# 2_DRAM.net
KiCad netlist of a schematic drawn in Altium Designer
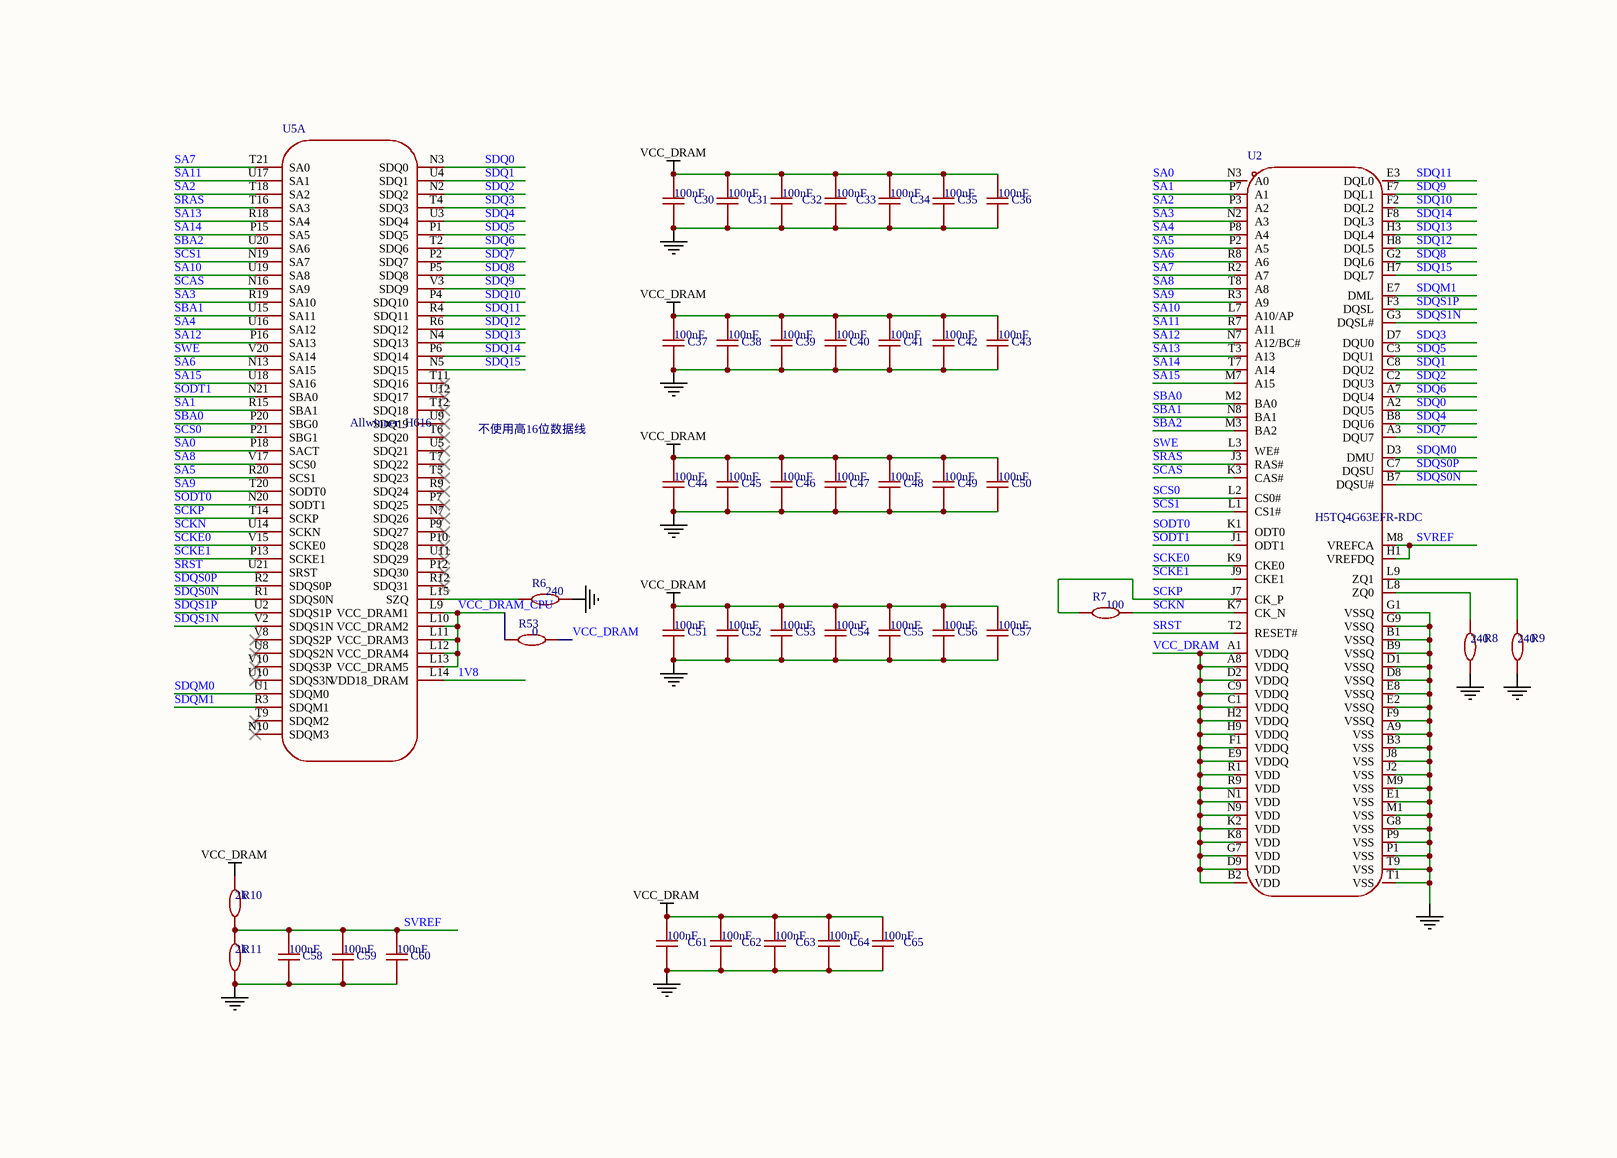
[diagram p0: 2_DRAM.schdoc]

(export (version "E")
  (design (tool "Eeschema 10.0.6"))
  (components
    (comp (ref "C30")
      (value "100nF")
      (footprint "PCB:C0402-NSK")
      (libsource (lib "PCB_Project") (part "CAP_0402"))
    )
    (comp (ref "C31")
      (value "100nF")
      (footprint "PCB:C0402-NSK")
      (libsource (lib "PCB_Project") (part "CAP_0402"))
    )
    (comp (ref "C32")
      (value "100nF")
      (footprint "PCB:C0402-NSK")
      (libsource (lib "PCB_Project") (part "CAP_0402"))
    )
    (comp (ref "C33")
      (value "100nF")
      (footprint "PCB:C0402-NSK")
      (libsource (lib "PCB_Project") (part "CAP_0402"))
    )
    (comp (ref "C34")
      (value "100nF")
      (footprint "PCB:C0402-NSK")
      (libsource (lib "PCB_Project") (part "CAP_0402"))
    )
    (comp (ref "C35")
      (value "100nF")
      (footprint "PCB:C0402-NSK")
      (libsource (lib "PCB_Project") (part "CAP_0402"))
    )
    (comp (ref "C36")
      (value "100nF")
      (footprint "PCB:C0402-NSK")
      (libsource (lib "PCB_Project") (part "CAP_0402"))
    )
    (comp (ref "C37")
      (value "100nF")
      (footprint "PCB:C0402-NSK")
      (libsource (lib "PCB_Project") (part "CAP_0402"))
    )
    (comp (ref "C38")
      (value "100nF")
      (footprint "PCB:C0402-NSK")
      (libsource (lib "PCB_Project") (part "CAP_0402"))
    )
    (comp (ref "C39")
      (value "100nF")
      (footprint "PCB:C0402-NSK")
      (libsource (lib "PCB_Project") (part "CAP_0402"))
    )
    (comp (ref "C40")
      (value "100nF")
      (footprint "PCB:C0402-NSK")
      (libsource (lib "PCB_Project") (part "CAP_0402"))
    )
    (comp (ref "C41")
      (value "100nF")
      (footprint "PCB:C0402-NSK")
      (libsource (lib "PCB_Project") (part "CAP_0402"))
    )
    (comp (ref "C42")
      (value "100nF")
      (footprint "PCB:C0402-NSK")
      (libsource (lib "PCB_Project") (part "CAP_0402"))
    )
    (comp (ref "C43")
      (value "100nF")
      (footprint "PCB:C0402-NSK")
      (libsource (lib "PCB_Project") (part "CAP_0402"))
    )
    (comp (ref "C44")
      (value "100nF")
      (footprint "PCB:C0402-NSK")
      (libsource (lib "PCB_Project") (part "CAP_0402"))
    )
    (comp (ref "C45")
      (value "100nF")
      (footprint "PCB:C0402-NSK")
      (libsource (lib "PCB_Project") (part "CAP_0402"))
    )
    (comp (ref "C46")
      (value "100nF")
      (footprint "PCB:C0402-NSK")
      (libsource (lib "PCB_Project") (part "CAP_0402"))
    )
    (comp (ref "C47")
      (value "100nF")
      (footprint "PCB:C0402-NSK")
      (libsource (lib "PCB_Project") (part "CAP_0402"))
    )
    (comp (ref "C48")
      (value "100nF")
      (footprint "PCB:C0402-NSK")
      (libsource (lib "PCB_Project") (part "CAP_0402"))
    )
    (comp (ref "C49")
      (value "100nF")
      (footprint "PCB:C0402-NSK")
      (libsource (lib "PCB_Project") (part "CAP_0402"))
    )
    (comp (ref "C50")
      (value "100nF")
      (footprint "PCB:C0402-NSK")
      (libsource (lib "PCB_Project") (part "CAP_0402"))
    )
    (comp (ref "C51")
      (value "100nF")
      (footprint "PCB:C0402-NSK")
      (libsource (lib "PCB_Project") (part "CAP_0402"))
    )
    (comp (ref "C52")
      (value "100nF")
      (footprint "PCB:C0402-NSK")
      (libsource (lib "PCB_Project") (part "CAP_0402"))
    )
    (comp (ref "C53")
      (value "100nF")
      (footprint "PCB:C0402-NSK")
      (libsource (lib "PCB_Project") (part "CAP_0402"))
    )
    (comp (ref "C54")
      (value "100nF")
      (footprint "PCB:C0402-NSK")
      (libsource (lib "PCB_Project") (part "CAP_0402"))
    )
    (comp (ref "C55")
      (value "100nF")
      (footprint "PCB:C0402-NSK")
      (libsource (lib "PCB_Project") (part "CAP_0402"))
    )
    (comp (ref "C56")
      (value "100nF")
      (footprint "PCB:C0402-NSK")
      (libsource (lib "PCB_Project") (part "CAP_0402"))
    )
    (comp (ref "C57")
      (value "100nF")
      (footprint "PCB:C0402-NSK")
      (libsource (lib "PCB_Project") (part "CAP_0402"))
    )
    (comp (ref "C58")
      (value "100nF")
      (footprint "PCB:C0402-NSK")
      (libsource (lib "PCB_Project") (part "CAP_0402"))
    )
    (comp (ref "C59")
      (value "100nF")
      (footprint "PCB:C0402-NSK")
      (libsource (lib "PCB_Project") (part "CAP_0402"))
    )
    (comp (ref "C60")
      (value "100nF")
      (footprint "PCB:C0402-NSK")
      (libsource (lib "PCB_Project") (part "CAP_0402"))
    )
    (comp (ref "C61")
      (value "100nF")
      (footprint "PCB:C0402-NSK")
      (libsource (lib "PCB_Project") (part "CAP_0402"))
    )
    (comp (ref "C62")
      (value "100nF")
      (footprint "PCB:C0402-NSK")
      (libsource (lib "PCB_Project") (part "CAP_0402"))
    )
    (comp (ref "C63")
      (value "100nF")
      (footprint "PCB:C0402-NSK")
      (libsource (lib "PCB_Project") (part "CAP_0402"))
    )
    (comp (ref "C64")
      (value "100nF")
      (footprint "PCB:C0402-NSK")
      (libsource (lib "PCB_Project") (part "CAP_0402"))
    )
    (comp (ref "C65")
      (value "100nF")
      (footprint "PCB:C0402-NSK")
      (libsource (lib "PCB_Project") (part "CAP_0402"))
    )
    (comp (ref "R6")
      (value "240")
      (footprint "PCB:R0402-NSK_2")
      (libsource (lib "PCB_Project") (part "Res_0402"))
    )
    (comp (ref "R7")
      (value "100")
      (footprint "PCB:R0402-NSK_2")
      (libsource (lib "PCB_Project") (part "Res_0402"))
    )
    (comp (ref "R8")
      (value "240")
      (footprint "PCB:R0402-NSK_2")
      (libsource (lib "PCB_Project") (part "Res_0402"))
    )
    (comp (ref "R9")
      (value "240")
      (footprint "PCB:R0402-NSK_2")
      (libsource (lib "PCB_Project") (part "Res_0402"))
    )
    (comp (ref "R10")
      (value "2k")
      (footprint "PCB:R0402-NSK_2")
      (libsource (lib "PCB_Project") (part "Res_0402"))
    )
    (comp (ref "R11")
      (value "2k")
      (footprint "PCB:R0402-NSK_2")
      (libsource (lib "PCB_Project") (part "Res_0402"))
    )
    (comp (ref "R53")
      (value "0")
      (footprint "PCB:R0402-NSK_2")
      (libsource (lib "PCB_Project") (part "Res_0402"))
    )
    (comp (ref "U2")
      (value "H5TQ4G63EFR-RDC")
      (footprint "PCB:FBGA96")
      (libsource (lib "PCB_Project") (part "H5TQ4G63EFR-RDC"))
    )
    (comp (ref "U5")
      (value "Allwinner_H616")
      (footprint "PCB:BGA284P65B1200_1400H125")
      (libsource (lib "PCB_Project") (part "Allwinner_H616"))
    )
  )
  (nets
    (net (code "1") (name "/1V8") (class "Default")
      (node (ref "U5") (pin "L14") (pinfunction "VDD18_DRAM_L14") (pintype "passive"))
    )
    (net (code "2") (name "/SA0") (class "Default")
      (node (ref "U2") (pin "N3") (pinfunction "A0_N3") (pintype "passive"))
      (node (ref "U5") (pin "P18") (pinfunction "SACT_P18") (pintype "passive"))
    )
    (net (code "3") (name "/SA1") (class "Default")
      (node (ref "U2") (pin "P7") (pinfunction "A1_P7") (pintype "passive"))
      (node (ref "U5") (pin "R15") (pinfunction "SBA1_R15") (pintype "passive"))
    )
    (net (code "4") (name "/SA2") (class "Default")
      (node (ref "U2") (pin "P3") (pinfunction "A2_P3") (pintype "passive"))
      (node (ref "U5") (pin "T18") (pinfunction "SA2_T18") (pintype "passive"))
    )
    (net (code "5") (name "/SA3") (class "Default")
      (node (ref "U2") (pin "N2") (pinfunction "A3_N2") (pintype "passive"))
      (node (ref "U5") (pin "R19") (pinfunction "SA10_R19") (pintype "passive"))
    )
    (net (code "6") (name "/SA4") (class "Default")
      (node (ref "U2") (pin "P8") (pinfunction "A4_P8") (pintype "passive"))
      (node (ref "U5") (pin "U16") (pinfunction "SA12_U16") (pintype "passive"))
    )
    (net (code "7") (name "/SA5") (class "Default")
      (node (ref "U2") (pin "P2") (pinfunction "A5_P2") (pintype "passive"))
      (node (ref "U5") (pin "R20") (pinfunction "SCS1_R20") (pintype "passive"))
    )
    (net (code "8") (name "/SA6") (class "Default")
      (node (ref "U2") (pin "R8") (pinfunction "A6_R8") (pintype "passive"))
      (node (ref "U5") (pin "N13") (pinfunction "SA15_N13") (pintype "passive"))
    )
    (net (code "9") (name "/SA7") (class "Default")
      (node (ref "U2") (pin "R2") (pinfunction "A7_R2") (pintype "passive"))
      (node (ref "U5") (pin "T21") (pinfunction "SA0_T21") (pintype "passive"))
    )
    (net (code "10") (name "/SA8") (class "Default")
      (node (ref "U2") (pin "T8") (pinfunction "A8_T8") (pintype "passive"))
      (node (ref "U5") (pin "V17") (pinfunction "SCS0_V17") (pintype "passive"))
    )
    (net (code "11") (name "/SA9") (class "Default")
      (node (ref "U2") (pin "R3") (pinfunction "A9_R3") (pintype "passive"))
      (node (ref "U5") (pin "T20") (pinfunction "SODT0_T20") (pintype "passive"))
    )
    (net (code "12") (name "/SA10") (class "Default")
      (node (ref "U2") (pin "L7") (pinfunction "A10/AP_L7") (pintype "passive"))
      (node (ref "U5") (pin "U19") (pinfunction "SA8_U19") (pintype "passive"))
    )
    (net (code "13") (name "/SA11") (class "Default")
      (node (ref "U2") (pin "R7") (pinfunction "A11_R7") (pintype "passive"))
      (node (ref "U5") (pin "U17") (pinfunction "SA1_U17") (pintype "passive"))
    )
    (net (code "14") (name "/SA12") (class "Default")
      (node (ref "U2") (pin "N7") (pinfunction "A12/BC#_N7") (pintype "passive"))
      (node (ref "U5") (pin "P16") (pinfunction "SA13_P16") (pintype "passive"))
    )
    (net (code "15") (name "/SA13") (class "Default")
      (node (ref "U2") (pin "T3") (pinfunction "A13_T3") (pintype "passive"))
      (node (ref "U5") (pin "R18") (pinfunction "SA4_R18") (pintype "passive"))
    )
    (net (code "16") (name "/SA14") (class "Default")
      (node (ref "U2") (pin "T7") (pinfunction "A14_T7") (pintype "passive"))
      (node (ref "U5") (pin "P15") (pinfunction "SA5_P15") (pintype "passive"))
    )
    (net (code "17") (name "/SA15") (class "Default")
      (node (ref "U2") (pin "M7") (pinfunction "A15_M7") (pintype "passive"))
      (node (ref "U5") (pin "U18") (pinfunction "SA16_U18") (pintype "passive"))
    )
    (net (code "18") (name "/SBA0") (class "Default")
      (node (ref "U2") (pin "M2") (pinfunction "BA0_M2") (pintype "passive"))
      (node (ref "U5") (pin "P20") (pinfunction "SBG0_P20") (pintype "passive"))
    )
    (net (code "19") (name "/SBA1") (class "Default")
      (node (ref "U2") (pin "N8") (pinfunction "BA1_N8") (pintype "passive"))
      (node (ref "U5") (pin "U15") (pinfunction "SA11_U15") (pintype "passive"))
    )
    (net (code "20") (name "/SBA2") (class "Default")
      (node (ref "U2") (pin "M3") (pinfunction "BA2_M3") (pintype "passive"))
      (node (ref "U5") (pin "U20") (pinfunction "SA6_U20") (pintype "passive"))
    )
    (net (code "21") (name "/SCAS") (class "Default")
      (node (ref "U2") (pin "K3") (pinfunction "CAS#_K3") (pintype "passive"))
      (node (ref "U5") (pin "N16") (pinfunction "SA9_N16") (pintype "passive"))
    )
    (net (code "22") (name "/SCKE0") (class "Default")
      (node (ref "U2") (pin "K9") (pinfunction "CKE0_K9") (pintype "passive"))
      (node (ref "U5") (pin "V15") (pinfunction "SCKE0_V15") (pintype "passive"))
    )
    (net (code "23") (name "/SCKE1") (class "Default")
      (node (ref "U2") (pin "J9") (pinfunction "CKE1_J9") (pintype "passive"))
      (node (ref "U5") (pin "P13") (pinfunction "SCKE1_P13") (pintype "passive"))
    )
    (net (code "24") (name "/SCKN") (class "Default")
      (node (ref "R7") (pin "2") (pinfunction "2_2") (pintype "passive"))
      (node (ref "U2") (pin "K7") (pinfunction "CK_N_K7") (pintype "passive"))
      (node (ref "U5") (pin "U14") (pinfunction "SCKN_U14") (pintype "passive"))
    )
    (net (code "25") (name "/SCKP") (class "Default")
      (node (ref "R7") (pin "1") (pinfunction "1_1") (pintype "passive"))
      (node (ref "U2") (pin "J7") (pinfunction "CK_P_J7") (pintype "passive"))
      (node (ref "U5") (pin "T14") (pinfunction "SCKP_T14") (pintype "passive"))
    )
    (net (code "26") (name "/SCS0") (class "Default")
      (node (ref "U2") (pin "L2") (pinfunction "CS0#_L2") (pintype "passive"))
      (node (ref "U5") (pin "P21") (pinfunction "SBG1_P21") (pintype "passive"))
    )
    (net (code "27") (name "/SCS1") (class "Default")
      (node (ref "U2") (pin "L1") (pinfunction "CS1#_L1") (pintype "passive"))
      (node (ref "U5") (pin "N19") (pinfunction "SA7_N19") (pintype "passive"))
    )
    (net (code "28") (name "/SDQ0") (class "Default")
      (node (ref "U2") (pin "A2") (pinfunction "DQU5_A2") (pintype "passive"))
      (node (ref "U5") (pin "N3") (pinfunction "SDQ0_N3") (pintype "passive"))
    )
    (net (code "29") (name "/SDQ1") (class "Default")
      (node (ref "U2") (pin "C8") (pinfunction "DQU2_C8") (pintype "passive"))
      (node (ref "U5") (pin "U4") (pinfunction "SDQ1_U4") (pintype "passive"))
    )
    (net (code "30") (name "/SDQ2") (class "Default")
      (node (ref "U2") (pin "C2") (pinfunction "DQU3_C2") (pintype "passive"))
      (node (ref "U5") (pin "N2") (pinfunction "SDQ2_N2") (pintype "passive"))
    )
    (net (code "31") (name "/SDQ3") (class "Default")
      (node (ref "U2") (pin "D7") (pinfunction "DQU0_D7") (pintype "passive"))
      (node (ref "U5") (pin "T4") (pinfunction "SDQ3_T4") (pintype "passive"))
    )
    (net (code "32") (name "/SDQ4") (class "Default")
      (node (ref "U2") (pin "B8") (pinfunction "DQU6_B8") (pintype "passive"))
      (node (ref "U5") (pin "U3") (pinfunction "SDQ4_U3") (pintype "passive"))
    )
    (net (code "33") (name "/SDQ5") (class "Default")
      (node (ref "U2") (pin "C3") (pinfunction "DQU1_C3") (pintype "passive"))
      (node (ref "U5") (pin "P1") (pinfunction "SDQ5_P1") (pintype "passive"))
    )
    (net (code "34") (name "/SDQ6") (class "Default")
      (node (ref "U2") (pin "A7") (pinfunction "DQU4_A7") (pintype "passive"))
      (node (ref "U5") (pin "T2") (pinfunction "SDQ6_T2") (pintype "passive"))
    )
    (net (code "35") (name "/SDQ7") (class "Default")
      (node (ref "U2") (pin "A3") (pinfunction "DQU7_A3") (pintype "passive"))
      (node (ref "U5") (pin "P2") (pinfunction "SDQ7_P2") (pintype "passive"))
    )
    (net (code "36") (name "/SDQ8") (class "Default")
      (node (ref "U2") (pin "G2") (pinfunction "DQL6_G2") (pintype "passive"))
      (node (ref "U5") (pin "P5") (pinfunction "SDQ8_P5") (pintype "passive"))
    )
    (net (code "37") (name "/SDQ9") (class "Default")
      (node (ref "U2") (pin "F7") (pinfunction "DQL1_F7") (pintype "passive"))
      (node (ref "U5") (pin "V3") (pinfunction "SDQ9_V3") (pintype "passive"))
    )
    (net (code "38") (name "/SDQ10") (class "Default")
      (node (ref "U2") (pin "F2") (pinfunction "DQL2_F2") (pintype "passive"))
      (node (ref "U5") (pin "P4") (pinfunction "SDQ10_P4") (pintype "passive"))
    )
    (net (code "39") (name "/SDQ11") (class "Default")
      (node (ref "U2") (pin "E3") (pinfunction "DQL0_E3") (pintype "passive"))
      (node (ref "U5") (pin "R4") (pinfunction "SDQ11_R4") (pintype "passive"))
    )
    (net (code "40") (name "/SDQ12") (class "Default")
      (node (ref "U2") (pin "H8") (pinfunction "DQL5_H8") (pintype "passive"))
      (node (ref "U5") (pin "R6") (pinfunction "SDQ12_R6") (pintype "passive"))
    )
    (net (code "41") (name "/SDQ13") (class "Default")
      (node (ref "U2") (pin "H3") (pinfunction "DQL4_H3") (pintype "passive"))
      (node (ref "U5") (pin "N4") (pinfunction "SDQ13_N4") (pintype "passive"))
    )
    (net (code "42") (name "/SDQ14") (class "Default")
      (node (ref "U2") (pin "F8") (pinfunction "DQL3_F8") (pintype "passive"))
      (node (ref "U5") (pin "P6") (pinfunction "SDQ14_P6") (pintype "passive"))
    )
    (net (code "43") (name "/SDQ15") (class "Default")
      (node (ref "U2") (pin "H7") (pinfunction "DQL7_H7") (pintype "passive"))
      (node (ref "U5") (pin "N5") (pinfunction "SDQ15_N5") (pintype "passive"))
    )
    (net (code "44") (name "/SDQM0") (class "Default")
      (node (ref "U2") (pin "D3") (pinfunction "DMU_D3") (pintype "passive"))
      (node (ref "U5") (pin "U1") (pinfunction "SDQM0_U1") (pintype "passive"))
    )
    (net (code "45") (name "/SDQM1") (class "Default")
      (node (ref "U2") (pin "E7") (pinfunction "DML_E7") (pintype "passive"))
      (node (ref "U5") (pin "R3") (pinfunction "SDQM1_R3") (pintype "passive"))
    )
    (net (code "46") (name "/SDQS0N") (class "Default")
      (node (ref "U2") (pin "B7") (pinfunction "DQSU#_B7") (pintype "passive"))
      (node (ref "U5") (pin "R1") (pinfunction "SDQS0N_R1") (pintype "passive"))
    )
    (net (code "47") (name "/SDQS0P") (class "Default")
      (node (ref "U2") (pin "C7") (pinfunction "DQSU_C7") (pintype "passive"))
      (node (ref "U5") (pin "R2") (pinfunction "SDQS0P_R2") (pintype "passive"))
    )
    (net (code "48") (name "/SDQS1N") (class "Default")
      (node (ref "U2") (pin "G3") (pinfunction "DQSL#_G3") (pintype "passive"))
      (node (ref "U5") (pin "V2") (pinfunction "SDQS1N_V2") (pintype "passive"))
    )
    (net (code "49") (name "/SDQS1P") (class "Default")
      (node (ref "U2") (pin "F3") (pinfunction "DQSL_F3") (pintype "passive"))
      (node (ref "U5") (pin "U2") (pinfunction "SDQS1P_U2") (pintype "passive"))
    )
    (net (code "50") (name "/SODT0") (class "Default")
      (node (ref "U2") (pin "K1") (pinfunction "ODT0_K1") (pintype "passive"))
      (node (ref "U5") (pin "N20") (pinfunction "SODT1_N20") (pintype "passive"))
    )
    (net (code "51") (name "/SODT1") (class "Default")
      (node (ref "U2") (pin "J1") (pinfunction "ODT1_J1") (pintype "passive"))
      (node (ref "U5") (pin "N21") (pinfunction "SBA0_N21") (pintype "passive"))
    )
    (net (code "52") (name "/SRAS") (class "Default")
      (node (ref "U2") (pin "J3") (pinfunction "RAS#_J3") (pintype "passive"))
      (node (ref "U5") (pin "T16") (pinfunction "SA3_T16") (pintype "passive"))
    )
    (net (code "53") (name "/SRST") (class "Default")
      (node (ref "U2") (pin "T2") (pinfunction "RESET#_T2") (pintype "passive"))
      (node (ref "U5") (pin "U21") (pinfunction "SRST_U21") (pintype "passive"))
    )
    (net (code "54") (name "/SVREF") (class "Default")
      (node (ref "C58") (pin "2") (pinfunction "2_2") (pintype "passive"))
      (node (ref "C59") (pin "2") (pinfunction "2_2") (pintype "passive"))
      (node (ref "C60") (pin "2") (pinfunction "2_2") (pintype "passive"))
      (node (ref "R10") (pin "1") (pinfunction "1_1") (pintype "passive"))
      (node (ref "R11") (pin "2") (pinfunction "2_2") (pintype "passive"))
      (node (ref "U2") (pin "H1") (pinfunction "VREFDQ_H1") (pintype "passive"))
      (node (ref "U2") (pin "M8") (pinfunction "VREFCA_M8") (pintype "passive"))
    )
    (net (code "55") (name "/SWE") (class "Default")
      (node (ref "U2") (pin "L3") (pinfunction "WE#_L3") (pintype "passive"))
      (node (ref "U5") (pin "V20") (pinfunction "SA14_V20") (pintype "passive"))
    )
    (net (code "56") (name "/VCC_DRAM_CPU") (class "Default")
      (node (ref "R53") (pin "1") (pinfunction "1_1") (pintype "passive"))
      (node (ref "U5") (pin "L10") (pinfunction "VCC_DRAM2_L10") (pintype "passive"))
      (node (ref "U5") (pin "L11") (pinfunction "VCC_DRAM3_L11") (pintype "passive"))
      (node (ref "U5") (pin "L12") (pinfunction "VCC_DRAM4_L12") (pintype "passive"))
      (node (ref "U5") (pin "L13") (pinfunction "VCC_DRAM5_L13") (pintype "passive"))
      (node (ref "U5") (pin "L9") (pinfunction "VCC_DRAM1_L9") (pintype "passive"))
    )
    (net (code "57") (name "GND") (class "Default")
      (node (ref "C30") (pin "1") (pinfunction "1_1") (pintype "passive"))
      (node (ref "C31") (pin "1") (pinfunction "1_1") (pintype "passive"))
      (node (ref "C32") (pin "1") (pinfunction "1_1") (pintype "passive"))
      (node (ref "C33") (pin "1") (pinfunction "1_1") (pintype "passive"))
      (node (ref "C34") (pin "1") (pinfunction "1_1") (pintype "passive"))
      (node (ref "C35") (pin "1") (pinfunction "1_1") (pintype "passive"))
      (node (ref "C36") (pin "1") (pinfunction "1_1") (pintype "passive"))
      (node (ref "C37") (pin "1") (pinfunction "1_1") (pintype "passive"))
      (node (ref "C38") (pin "1") (pinfunction "1_1") (pintype "passive"))
      (node (ref "C39") (pin "1") (pinfunction "1_1") (pintype "passive"))
      (node (ref "C40") (pin "1") (pinfunction "1_1") (pintype "passive"))
      (node (ref "C41") (pin "1") (pinfunction "1_1") (pintype "passive"))
      (node (ref "C42") (pin "1") (pinfunction "1_1") (pintype "passive"))
      (node (ref "C43") (pin "1") (pinfunction "1_1") (pintype "passive"))
      (node (ref "C44") (pin "1") (pinfunction "1_1") (pintype "passive"))
      (node (ref "C45") (pin "1") (pinfunction "1_1") (pintype "passive"))
      (node (ref "C46") (pin "1") (pinfunction "1_1") (pintype "passive"))
      (node (ref "C47") (pin "1") (pinfunction "1_1") (pintype "passive"))
      (node (ref "C48") (pin "1") (pinfunction "1_1") (pintype "passive"))
      (node (ref "C49") (pin "1") (pinfunction "1_1") (pintype "passive"))
      (node (ref "C50") (pin "1") (pinfunction "1_1") (pintype "passive"))
      (node (ref "C51") (pin "1") (pinfunction "1_1") (pintype "passive"))
      (node (ref "C52") (pin "1") (pinfunction "1_1") (pintype "passive"))
      (node (ref "C53") (pin "1") (pinfunction "1_1") (pintype "passive"))
      (node (ref "C54") (pin "1") (pinfunction "1_1") (pintype "passive"))
      (node (ref "C55") (pin "1") (pinfunction "1_1") (pintype "passive"))
      (node (ref "C56") (pin "1") (pinfunction "1_1") (pintype "passive"))
      (node (ref "C57") (pin "1") (pinfunction "1_1") (pintype "passive"))
      (node (ref "C58") (pin "1") (pinfunction "1_1") (pintype "passive"))
      (node (ref "C59") (pin "1") (pinfunction "1_1") (pintype "passive"))
      (node (ref "C60") (pin "1") (pinfunction "1_1") (pintype "passive"))
      (node (ref "C61") (pin "1") (pinfunction "1_1") (pintype "passive"))
      (node (ref "C62") (pin "1") (pinfunction "1_1") (pintype "passive"))
      (node (ref "C63") (pin "1") (pinfunction "1_1") (pintype "passive"))
      (node (ref "C64") (pin "1") (pinfunction "1_1") (pintype "passive"))
      (node (ref "C65") (pin "1") (pinfunction "1_1") (pintype "passive"))
      (node (ref "R11") (pin "1") (pinfunction "1_1") (pintype "passive"))
      (node (ref "R6") (pin "2") (pinfunction "2_2") (pintype "passive"))
      (node (ref "R8") (pin "1") (pinfunction "1_1") (pintype "passive"))
      (node (ref "R9") (pin "1") (pinfunction "1_1") (pintype "passive"))
      (node (ref "U2") (pin "A9") (pinfunction "VSS_A9") (pintype "passive"))
      (node (ref "U2") (pin "B1") (pinfunction "VSSQ_B1") (pintype "passive"))
      (node (ref "U2") (pin "B3") (pinfunction "VSS_B3") (pintype "passive"))
      (node (ref "U2") (pin "B9") (pinfunction "VSSQ_B9") (pintype "passive"))
      (node (ref "U2") (pin "D1") (pinfunction "VSSQ_D1") (pintype "passive"))
      (node (ref "U2") (pin "D8") (pinfunction "VSSQ_D8") (pintype "passive"))
      (node (ref "U2") (pin "E1") (pinfunction "VSS_E1") (pintype "passive"))
      (node (ref "U2") (pin "E2") (pinfunction "VSSQ_E2") (pintype "passive"))
      (node (ref "U2") (pin "E8") (pinfunction "VSSQ_E8") (pintype "passive"))
      (node (ref "U2") (pin "F9") (pinfunction "VSSQ_F9") (pintype "passive"))
      (node (ref "U2") (pin "G1") (pinfunction "VSSQ_G1") (pintype "passive"))
      (node (ref "U2") (pin "G8") (pinfunction "VSS_G8") (pintype "passive"))
      (node (ref "U2") (pin "G9") (pinfunction "VSSQ_G9") (pintype "passive"))
      (node (ref "U2") (pin "J2") (pinfunction "VSS_J2") (pintype "passive"))
      (node (ref "U2") (pin "J8") (pinfunction "VSS_J8") (pintype "passive"))
      (node (ref "U2") (pin "M1") (pinfunction "VSS_M1") (pintype "passive"))
      (node (ref "U2") (pin "M9") (pinfunction "VSS_M9") (pintype "passive"))
      (node (ref "U2") (pin "P1") (pinfunction "VSS_P1") (pintype "passive"))
      (node (ref "U2") (pin "P9") (pinfunction "VSS_P9") (pintype "passive"))
      (node (ref "U2") (pin "T1") (pinfunction "VSS_T1") (pintype "passive"))
      (node (ref "U2") (pin "T9") (pinfunction "VSS_T9") (pintype "passive"))
    )
    (net (code "58") (name "Net-(U2-ZQ0)") (class "Default")
      (node (ref "R8") (pin "2") (pinfunction "2_2") (pintype "passive"))
      (node (ref "U2") (pin "L8") (pinfunction "ZQ0_L8") (pintype "passive"))
    )
    (net (code "59") (name "Net-(U2-ZQ1)") (class "Default")
      (node (ref "R9") (pin "2") (pinfunction "2_2") (pintype "passive"))
      (node (ref "U2") (pin "L9") (pinfunction "ZQ1_L9") (pintype "passive"))
    )
    (net (code "60") (name "Net-(U5A-SZQ)") (class "Default")
      (node (ref "R6") (pin "1") (pinfunction "1_1") (pintype "passive"))
      (node (ref "U5") (pin "L15") (pinfunction "SZQ_L15") (pintype "passive"))
    )
    (net (code "61") (name "VCC_DRAM") (class "Default")
      (node (ref "C30") (pin "2") (pinfunction "2_2") (pintype "passive"))
      (node (ref "C31") (pin "2") (pinfunction "2_2") (pintype "passive"))
      (node (ref "C32") (pin "2") (pinfunction "2_2") (pintype "passive"))
      (node (ref "C33") (pin "2") (pinfunction "2_2") (pintype "passive"))
      (node (ref "C34") (pin "2") (pinfunction "2_2") (pintype "passive"))
      (node (ref "C35") (pin "2") (pinfunction "2_2") (pintype "passive"))
      (node (ref "C36") (pin "2") (pinfunction "2_2") (pintype "passive"))
      (node (ref "C37") (pin "2") (pinfunction "2_2") (pintype "passive"))
      (node (ref "C38") (pin "2") (pinfunction "2_2") (pintype "passive"))
      (node (ref "C39") (pin "2") (pinfunction "2_2") (pintype "passive"))
      (node (ref "C40") (pin "2") (pinfunction "2_2") (pintype "passive"))
      (node (ref "C41") (pin "2") (pinfunction "2_2") (pintype "passive"))
      (node (ref "C42") (pin "2") (pinfunction "2_2") (pintype "passive"))
      (node (ref "C43") (pin "2") (pinfunction "2_2") (pintype "passive"))
      (node (ref "C44") (pin "2") (pinfunction "2_2") (pintype "passive"))
      (node (ref "C45") (pin "2") (pinfunction "2_2") (pintype "passive"))
      (node (ref "C46") (pin "2") (pinfunction "2_2") (pintype "passive"))
      (node (ref "C47") (pin "2") (pinfunction "2_2") (pintype "passive"))
      (node (ref "C48") (pin "2") (pinfunction "2_2") (pintype "passive"))
      (node (ref "C49") (pin "2") (pinfunction "2_2") (pintype "passive"))
      (node (ref "C50") (pin "2") (pinfunction "2_2") (pintype "passive"))
      (node (ref "C51") (pin "2") (pinfunction "2_2") (pintype "passive"))
      (node (ref "C52") (pin "2") (pinfunction "2_2") (pintype "passive"))
      (node (ref "C53") (pin "2") (pinfunction "2_2") (pintype "passive"))
      (node (ref "C54") (pin "2") (pinfunction "2_2") (pintype "passive"))
      (node (ref "C55") (pin "2") (pinfunction "2_2") (pintype "passive"))
      (node (ref "C56") (pin "2") (pinfunction "2_2") (pintype "passive"))
      (node (ref "C57") (pin "2") (pinfunction "2_2") (pintype "passive"))
      (node (ref "C61") (pin "2") (pinfunction "2_2") (pintype "passive"))
      (node (ref "C62") (pin "2") (pinfunction "2_2") (pintype "passive"))
      (node (ref "C63") (pin "2") (pinfunction "2_2") (pintype "passive"))
      (node (ref "C64") (pin "2") (pinfunction "2_2") (pintype "passive"))
      (node (ref "C65") (pin "2") (pinfunction "2_2") (pintype "passive"))
      (node (ref "R10") (pin "2") (pinfunction "2_2") (pintype "passive"))
      (node (ref "R53") (pin "2") (pinfunction "2_2") (pintype "passive"))
      (node (ref "U2") (pin "A1") (pinfunction "VDDQ_A1") (pintype "passive"))
      (node (ref "U2") (pin "A8") (pinfunction "VDDQ_A8") (pintype "passive"))
      (node (ref "U2") (pin "B2") (pinfunction "VDD_B2") (pintype "passive"))
      (node (ref "U2") (pin "C1") (pinfunction "VDDQ_C1") (pintype "passive"))
      (node (ref "U2") (pin "C9") (pinfunction "VDDQ_C9") (pintype "passive"))
      (node (ref "U2") (pin "D2") (pinfunction "VDDQ_D2") (pintype "passive"))
      (node (ref "U2") (pin "D9") (pinfunction "VDD_D9") (pintype "passive"))
      (node (ref "U2") (pin "E9") (pinfunction "VDDQ_E9") (pintype "passive"))
      (node (ref "U2") (pin "F1") (pinfunction "VDDQ_F1") (pintype "passive"))
      (node (ref "U2") (pin "G7") (pinfunction "VDD_G7") (pintype "passive"))
      (node (ref "U2") (pin "H2") (pinfunction "VDDQ_H2") (pintype "passive"))
      (node (ref "U2") (pin "H9") (pinfunction "VDDQ_H9") (pintype "passive"))
      (node (ref "U2") (pin "K2") (pinfunction "VDD_K2") (pintype "passive"))
      (node (ref "U2") (pin "K8") (pinfunction "VDD_K8") (pintype "passive"))
      (node (ref "U2") (pin "N1") (pinfunction "VDD_N1") (pintype "passive"))
      (node (ref "U2") (pin "N9") (pinfunction "VDD_N9") (pintype "passive"))
      (node (ref "U2") (pin "R1") (pinfunction "VDD_R1") (pintype "passive"))
      (node (ref "U2") (pin "R9") (pinfunction "VDD_R9") (pintype "passive"))
    )
    (net (code "62") (name "unconnected-(U5A-SDQ16-PadT11)") (class "Default")
      (node (ref "U5") (pin "T11") (pinfunction "SDQ16_T11") (pintype "passive+no_connect"))
    )
    (net (code "63") (name "unconnected-(U5A-SDQ17-PadU12)") (class "Default")
      (node (ref "U5") (pin "U12") (pinfunction "SDQ17_U12") (pintype "passive+no_connect"))
    )
    (net (code "64") (name "unconnected-(U5A-SDQ18-PadT12)") (class "Default")
      (node (ref "U5") (pin "T12") (pinfunction "SDQ18_T12") (pintype "passive+no_connect"))
    )
    (net (code "65") (name "unconnected-(U5A-SDQ19-PadU9)") (class "Default")
      (node (ref "U5") (pin "U9") (pinfunction "SDQ19_U9") (pintype "passive+no_connect"))
    )
    (net (code "66") (name "unconnected-(U5A-SDQ20-PadT6)") (class "Default")
      (node (ref "U5") (pin "T6") (pinfunction "SDQ20_T6") (pintype "passive+no_connect"))
    )
    (net (code "67") (name "unconnected-(U5A-SDQ21-PadU5)") (class "Default")
      (node (ref "U5") (pin "U5") (pinfunction "SDQ21_U5") (pintype "passive+no_connect"))
    )
    (net (code "68") (name "unconnected-(U5A-SDQ22-PadT7)") (class "Default")
      (node (ref "U5") (pin "T7") (pinfunction "SDQ22_T7") (pintype "passive+no_connect"))
    )
    (net (code "69") (name "unconnected-(U5A-SDQ23-PadT5)") (class "Default")
      (node (ref "U5") (pin "T5") (pinfunction "SDQ23_T5") (pintype "passive+no_connect"))
    )
    (net (code "70") (name "unconnected-(U5A-SDQ24-PadR9)") (class "Default")
      (node (ref "U5") (pin "R9") (pinfunction "SDQ24_R9") (pintype "passive+no_connect"))
    )
    (net (code "71") (name "unconnected-(U5A-SDQ25-PadP7)") (class "Default")
      (node (ref "U5") (pin "P7") (pinfunction "SDQ25_P7") (pintype "passive+no_connect"))
    )
    (net (code "72") (name "unconnected-(U5A-SDQ26-PadN7)") (class "Default")
      (node (ref "U5") (pin "N7") (pinfunction "SDQ26_N7") (pintype "passive+no_connect"))
    )
    (net (code "73") (name "unconnected-(U5A-SDQ27-PadP9)") (class "Default")
      (node (ref "U5") (pin "P9") (pinfunction "SDQ27_P9") (pintype "passive+no_connect"))
    )
    (net (code "74") (name "unconnected-(U5A-SDQ28-PadP10)") (class "Default")
      (node (ref "U5") (pin "P10") (pinfunction "SDQ28_P10") (pintype "passive+no_connect"))
    )
    (net (code "75") (name "unconnected-(U5A-SDQ29-PadU11)") (class "Default")
      (node (ref "U5") (pin "U11") (pinfunction "SDQ29_U11") (pintype "passive+no_connect"))
    )
    (net (code "76") (name "unconnected-(U5A-SDQ30-PadP12)") (class "Default")
      (node (ref "U5") (pin "P12") (pinfunction "SDQ30_P12") (pintype "passive+no_connect"))
    )
    (net (code "77") (name "unconnected-(U5A-SDQ31-PadR12)") (class "Default")
      (node (ref "U5") (pin "R12") (pinfunction "SDQ31_R12") (pintype "passive+no_connect"))
    )
    (net (code "78") (name "unconnected-(U5A-SDQM2-PadT9)") (class "Default")
      (node (ref "U5") (pin "T9") (pinfunction "SDQM2_T9") (pintype "passive+no_connect"))
    )
    (net (code "79") (name "unconnected-(U5A-SDQM3-PadN10)") (class "Default")
      (node (ref "U5") (pin "N10") (pinfunction "SDQM3_N10") (pintype "passive+no_connect"))
    )
    (net (code "80") (name "unconnected-(U5A-SDQS2N-PadU8)") (class "Default")
      (node (ref "U5") (pin "U8") (pinfunction "SDQS2N_U8") (pintype "passive+no_connect"))
    )
    (net (code "81") (name "unconnected-(U5A-SDQS2P-PadV8)") (class "Default")
      (node (ref "U5") (pin "V8") (pinfunction "SDQS2P_V8") (pintype "passive+no_connect"))
    )
    (net (code "82") (name "unconnected-(U5A-SDQS3N-PadU10)") (class "Default")
      (node (ref "U5") (pin "U10") (pinfunction "SDQS3N_U10") (pintype "passive+no_connect"))
    )
    (net (code "83") (name "unconnected-(U5A-SDQS3P-PadV10)") (class "Default")
      (node (ref "U5") (pin "V10") (pinfunction "SDQS3P_V10") (pintype "passive+no_connect"))
    )
  )
)
